# top5v.net
KiCad netlist of a schematic drawn in EAGLE
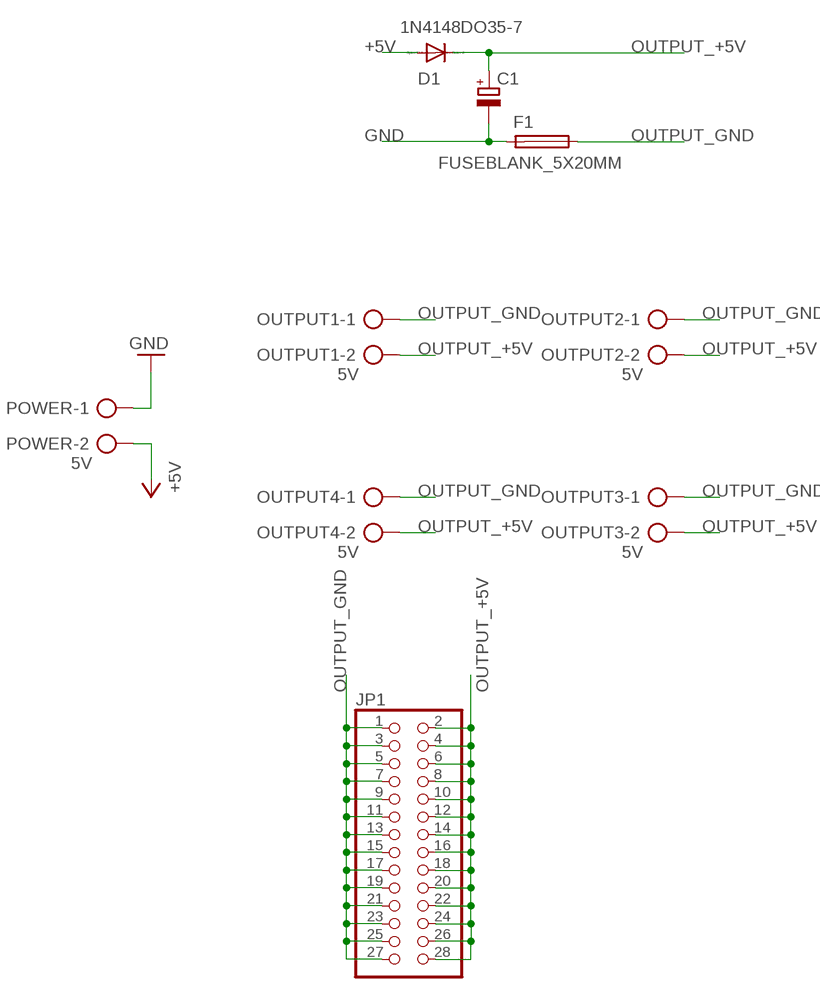
[diagram p0: schematic, sheet 1]

(export (version "E")
  (design (tool "Eeschema 10.0.6"))
  (components
    (comp (ref "C1")
      (value "CPOL-EUE1.8-4")
      (footprint "eagle-import:E1,8-4")
      (libsource (lib "eagle-import") (part "CPOL-EUE1.8-4"))
    )
    (comp (ref "D1")
      (value "1N4148DO35-7")
      (footprint "eagle-import:DO35-7")
      (libsource (lib "eagle-import") (part "1N4148DO35-7"))
    )
    (comp (ref "F1")
      (value "FUSEBLANK_5X20MM")
      (footprint "eagle-import:FUSE_HOLDER_5X20MM")
      (libsource (lib "eagle-import") (part "FUSEBLANK_5X20MM"))
    )
    (comp (ref "JP1")
      (value "PINHD-2X14")
      (footprint "eagle-import:2X14")
      (libsource (lib "eagle-import") (part "PINHD-2X14"))
    )
    (comp (ref "OUTPUT1")
      (value "5V")
      (footprint "eagle-import:AK500_2-H")
      (libsource (lib "eagle-import") (part "AK500/2-H"))
    )
    (comp (ref "OUTPUT2")
      (value "5V")
      (footprint "eagle-import:AK500_2-H")
      (libsource (lib "eagle-import") (part "AK500/2-H"))
    )
    (comp (ref "OUTPUT3")
      (value "5V")
      (footprint "eagle-import:AK500_2-H")
      (libsource (lib "eagle-import") (part "AK500/2-H"))
    )
    (comp (ref "OUTPUT4")
      (value "5V")
      (footprint "eagle-import:AK500_2-H")
      (libsource (lib "eagle-import") (part "AK500/2-H"))
    )
    (comp (ref "POWER")
      (value "5V")
      (footprint "eagle-import:AK500_2-H")
      (libsource (lib "eagle-import") (part "AK500/2-H"))
    )
  )
  (nets
    (net (code "1") (name "+5V") (class "Default")
      (node (ref "D1") (pin "A") (pinfunction "A_A") (pintype "passive"))
      (node (ref "POWER") (pin "2") (pinfunction "KL_2") (pintype "passive"))
    )
    (net (code "2") (name "/OUTPUT_+5V") (class "Default")
      (node (ref "C1") (pin "+") (pinfunction "+_+") (pintype "passive"))
      (node (ref "D1") (pin "C") (pinfunction "C_C") (pintype "passive"))
      (node (ref "JP1") (pin "10") (pinfunction "10_10") (pintype "passive"))
      (node (ref "JP1") (pin "12") (pinfunction "12_12") (pintype "passive"))
      (node (ref "JP1") (pin "14") (pinfunction "14_14") (pintype "passive"))
      (node (ref "JP1") (pin "16") (pinfunction "16_16") (pintype "passive"))
      (node (ref "JP1") (pin "18") (pinfunction "18_18") (pintype "passive"))
      (node (ref "JP1") (pin "2") (pinfunction "2_2") (pintype "passive"))
      (node (ref "JP1") (pin "20") (pinfunction "20_20") (pintype "passive"))
      (node (ref "JP1") (pin "22") (pinfunction "22_22") (pintype "passive"))
      (node (ref "JP1") (pin "24") (pinfunction "24_24") (pintype "passive"))
      (node (ref "JP1") (pin "26") (pinfunction "26_26") (pintype "passive"))
      (node (ref "JP1") (pin "28") (pinfunction "28_28") (pintype "passive"))
      (node (ref "JP1") (pin "4") (pinfunction "4_4") (pintype "passive"))
      (node (ref "JP1") (pin "6") (pinfunction "6_6") (pintype "passive"))
      (node (ref "JP1") (pin "8") (pinfunction "8_8") (pintype "passive"))
      (node (ref "OUTPUT1") (pin "2") (pinfunction "KL_2") (pintype "passive"))
      (node (ref "OUTPUT2") (pin "2") (pinfunction "KL_2") (pintype "passive"))
      (node (ref "OUTPUT3") (pin "2") (pinfunction "KL_2") (pintype "passive"))
      (node (ref "OUTPUT4") (pin "2") (pinfunction "KL_2") (pintype "passive"))
    )
    (net (code "3") (name "/OUTPUT_GND") (class "Default")
      (node (ref "F1") (pin "1") (pinfunction "1_1") (pintype "passive"))
      (node (ref "JP1") (pin "1") (pinfunction "1_1") (pintype "passive"))
      (node (ref "JP1") (pin "11") (pinfunction "11_11") (pintype "passive"))
      (node (ref "JP1") (pin "13") (pinfunction "13_13") (pintype "passive"))
      (node (ref "JP1") (pin "15") (pinfunction "15_15") (pintype "passive"))
      (node (ref "JP1") (pin "17") (pinfunction "17_17") (pintype "passive"))
      (node (ref "JP1") (pin "19") (pinfunction "19_19") (pintype "passive"))
      (node (ref "JP1") (pin "21") (pinfunction "21_21") (pintype "passive"))
      (node (ref "JP1") (pin "23") (pinfunction "23_23") (pintype "passive"))
      (node (ref "JP1") (pin "25") (pinfunction "25_25") (pintype "passive"))
      (node (ref "JP1") (pin "27") (pinfunction "27_27") (pintype "passive"))
      (node (ref "JP1") (pin "3") (pinfunction "3_3") (pintype "passive"))
      (node (ref "JP1") (pin "5") (pinfunction "5_5") (pintype "passive"))
      (node (ref "JP1") (pin "7") (pinfunction "7_7") (pintype "passive"))
      (node (ref "JP1") (pin "9") (pinfunction "9_9") (pintype "passive"))
      (node (ref "OUTPUT1") (pin "1") (pinfunction "KL_1") (pintype "passive"))
      (node (ref "OUTPUT2") (pin "1") (pinfunction "KL_1") (pintype "passive"))
      (node (ref "OUTPUT3") (pin "1") (pinfunction "KL_1") (pintype "passive"))
      (node (ref "OUTPUT4") (pin "1") (pinfunction "KL_1") (pintype "passive"))
    )
    (net (code "4") (name "GND") (class "Default")
      (node (ref "C1") (pin "-") (pinfunction "-_-") (pintype "passive"))
      (node (ref "F1") (pin "2") (pinfunction "2_2") (pintype "passive"))
      (node (ref "POWER") (pin "1") (pinfunction "KL_1") (pintype "passive"))
    )
  )
)
